# main.net
KiCad netlist of a schematic drawn in EAGLE
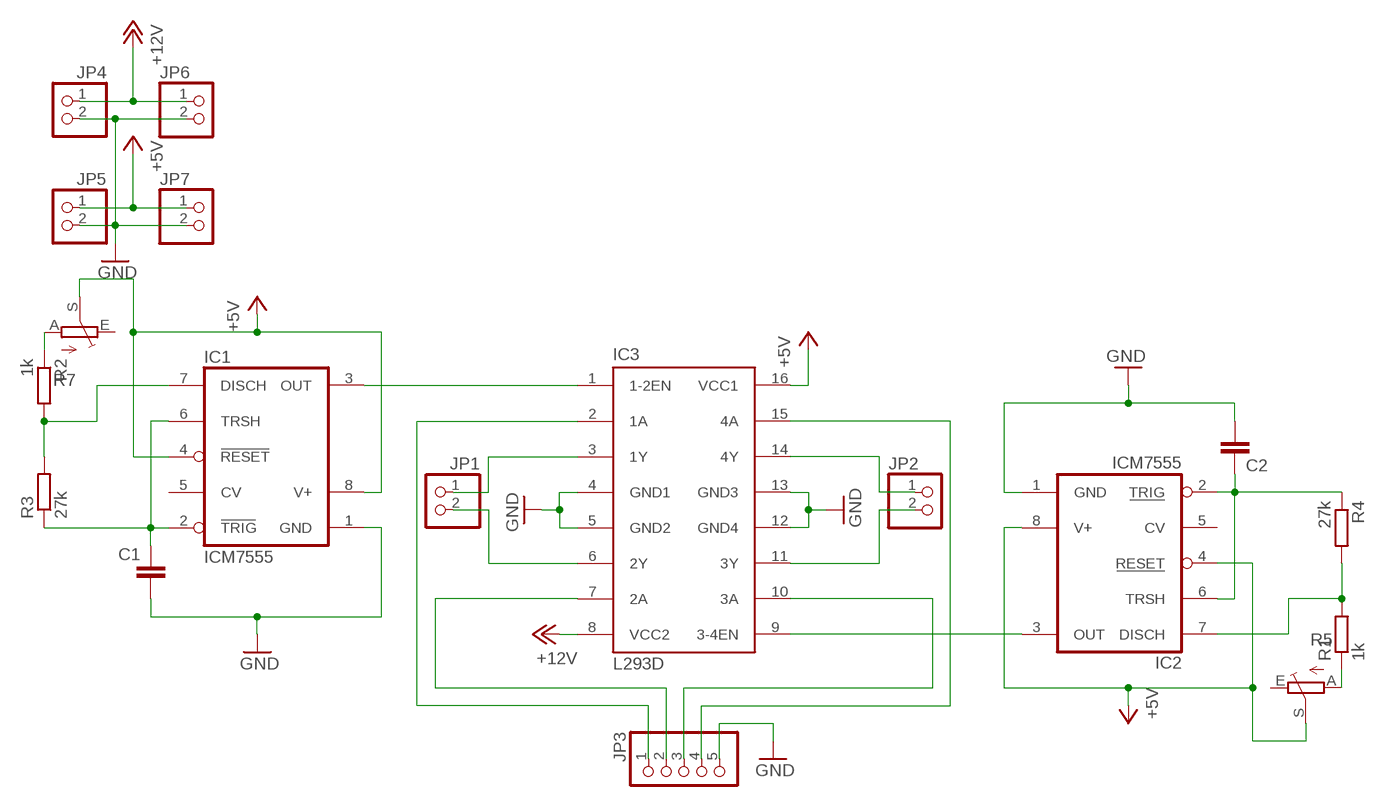
[diagram p0: schematic, sheet 1]

(export (version "E")
  (design (tool "Eeschema 10.0.6"))
  (components
    (comp (ref "C1")
      (value "C-EU025-025X050")
      (footprint "eagle-import:C025-025X050")
      (libsource (lib "eagle-import") (part "C-EU025-025X050"))
    )
    (comp (ref "C2")
      (value "C-EU025-025X050")
      (footprint "eagle-import:C025-025X050")
      (libsource (lib "eagle-import") (part "C-EU025-025X050"))
    )
    (comp (ref "IC1")
      (value "ICM7555")
      (footprint "eagle-import:DIL08")
      (fields (field (name "MF") "MAXIM") (field (name "MPN") "ICM7555IPA+"))
      (libsource (lib "eagle-import") (part "ICM7555"))
    )
    (comp (ref "IC2")
      (value "ICM7555")
      (footprint "eagle-import:DIL08")
      (fields (field (name "MF") "MAXIM") (field (name "MPN") "ICM7555IPA+"))
      (libsource (lib "eagle-import") (part "ICM7555"))
    )
    (comp (ref "IC3")
      (value "L293D")
      (footprint "eagle-import:DIL16")
      (libsource (lib "eagle-import") (part "L293D"))
    )
    (comp (ref "JP1")
      (value "PINHD-1X2")
      (footprint "eagle-import:1X02")
      (libsource (lib "eagle-import") (part "PINHD-1X2"))
    )
    (comp (ref "JP2")
      (value "PINHD-1X2")
      (footprint "eagle-import:1X02")
      (libsource (lib "eagle-import") (part "PINHD-1X2"))
    )
    (comp (ref "JP3")
      (value "PINHD-1X5")
      (footprint "eagle-import:1X05")
      (libsource (lib "eagle-import") (part "PINHD-1X5"))
    )
    (comp (ref "JP4")
      (value "PINHD-1X2")
      (footprint "eagle-import:1X02")
      (libsource (lib "eagle-import") (part "PINHD-1X2"))
    )
    (comp (ref "JP5")
      (value "PINHD-1X2")
      (footprint "eagle-import:1X02")
      (libsource (lib "eagle-import") (part "PINHD-1X2"))
    )
    (comp (ref "JP6")
      (value "PINHD-1X2")
      (footprint "eagle-import:1X02")
      (libsource (lib "eagle-import") (part "PINHD-1X2"))
    )
    (comp (ref "JP7")
      (value "PINHD-1X2")
      (footprint "eagle-import:1X02")
      (libsource (lib "eagle-import") (part "PINHD-1X2"))
    )
    (comp (ref "R1")
      (value "1k")
      (footprint "eagle-import:0204_7")
      (libsource (lib "eagle-import") (part "R-EU_0204/7"))
    )
    (comp (ref "R2")
      (value "1k")
      (footprint "eagle-import:0204_7")
      (libsource (lib "eagle-import") (part "R-EU_0204/7"))
    )
    (comp (ref "R3")
      (value "27k")
      (footprint "eagle-import:0204_7")
      (libsource (lib "eagle-import") (part "R-EU_0204/7"))
    )
    (comp (ref "R4")
      (value "27k")
      (footprint "eagle-import:0204_7")
      (libsource (lib "eagle-import") (part "R-EU_0204/7"))
    )
    (comp (ref "R5")
      (value "TRIM_EU-LI15")
      (footprint "eagle-import:LI15")
      (libsource (lib "eagle-import") (part "TRIM_EU-LI15"))
    )
    (comp (ref "R7")
      (value "TRIM_EU-LI15")
      (footprint "eagle-import:LI15")
      (libsource (lib "eagle-import") (part "TRIM_EU-LI15"))
    )
  )
  (nets
    (net (code "1") (name "+5V") (class "Default")
      (node (ref "IC1") (pin "4") (pinfunction "RESET_4") (pintype "input"))
      (node (ref "IC1") (pin "8") (pinfunction "V+_8") (pintype "power_in"))
      (node (ref "IC2") (pin "4") (pinfunction "RESET_4") (pintype "input"))
      (node (ref "IC2") (pin "8") (pinfunction "V+_8") (pintype "power_in"))
      (node (ref "IC3") (pin "16") (pinfunction "VCC1_16") (pintype "power_in"))
      (node (ref "JP5") (pin "1") (pinfunction "1_1") (pintype "passive"))
      (node (ref "JP7") (pin "1") (pinfunction "1_1") (pintype "passive"))
      (node (ref "R5") (pin "S") (pinfunction "S_S") (pintype "passive"))
      (node (ref "R7") (pin "S") (pinfunction "S_S") (pintype "passive"))
    )
    (net (code "2") (name "+12V") (class "Default")
      (node (ref "IC3") (pin "8") (pinfunction "VCC2_8") (pintype "power_in"))
      (node (ref "JP4") (pin "1") (pinfunction "1_1") (pintype "passive"))
      (node (ref "JP6") (pin "1") (pinfunction "1_1") (pintype "passive"))
    )
    (net (code "3") (name "GND") (class "Default")
      (node (ref "C1") (pin "2") (pinfunction "2_2") (pintype "passive"))
      (node (ref "C2") (pin "2") (pinfunction "2_2") (pintype "passive"))
      (node (ref "IC1") (pin "1") (pinfunction "GND_1") (pintype "power_in"))
      (node (ref "IC2") (pin "1") (pinfunction "GND_1") (pintype "power_in"))
      (node (ref "IC3") (pin "12") (pinfunction "GND4_12") (pintype "power_in"))
      (node (ref "IC3") (pin "13") (pinfunction "GND3_13") (pintype "power_in"))
      (node (ref "IC3") (pin "4") (pinfunction "GND1_4") (pintype "power_in"))
      (node (ref "IC3") (pin "5") (pinfunction "GND2_5") (pintype "power_in"))
      (node (ref "JP3") (pin "5") (pinfunction "5_5") (pintype "passive"))
      (node (ref "JP4") (pin "2") (pinfunction "2_2") (pintype "passive"))
      (node (ref "JP5") (pin "2") (pinfunction "2_2") (pintype "passive"))
      (node (ref "JP6") (pin "2") (pinfunction "2_2") (pintype "passive"))
      (node (ref "JP7") (pin "2") (pinfunction "2_2") (pintype "passive"))
    )
    (net (code "4") (name "Net-(IC1-DISCH)") (class "Default")
      (node (ref "IC1") (pin "7") (pinfunction "DISCH_7") (pintype "input"))
      (node (ref "R2") (pin "2") (pinfunction "2_2") (pintype "passive"))
      (node (ref "R3") (pin "2") (pinfunction "2_2") (pintype "passive"))
    )
    (net (code "5") (name "Net-(IC1-OUT)") (class "Default")
      (node (ref "IC1") (pin "3") (pinfunction "OUT_3") (pintype "output"))
      (node (ref "IC3") (pin "1") (pinfunction "1-2EN_1") (pintype "input"))
    )
    (net (code "6") (name "Net-(IC1-TRIG)") (class "Default")
      (node (ref "C1") (pin "1") (pinfunction "1_1") (pintype "passive"))
      (node (ref "IC1") (pin "2") (pinfunction "TRIG_2") (pintype "bidirectional"))
      (node (ref "IC1") (pin "6") (pinfunction "TRSH_6") (pintype "input"))
      (node (ref "R3") (pin "1") (pinfunction "1_1") (pintype "passive"))
    )
    (net (code "7") (name "Net-(IC2-DISCH)") (class "Default")
      (node (ref "IC2") (pin "7") (pinfunction "DISCH_7") (pintype "input"))
      (node (ref "R1") (pin "2") (pinfunction "2_2") (pintype "passive"))
      (node (ref "R4") (pin "2") (pinfunction "2_2") (pintype "passive"))
    )
    (net (code "8") (name "Net-(IC2-OUT)") (class "Default")
      (node (ref "IC2") (pin "3") (pinfunction "OUT_3") (pintype "output"))
      (node (ref "IC3") (pin "9") (pinfunction "3-4EN_9") (pintype "input"))
    )
    (net (code "9") (name "Net-(IC2-TRIG)") (class "Default")
      (node (ref "C2") (pin "1") (pinfunction "1_1") (pintype "passive"))
      (node (ref "IC2") (pin "2") (pinfunction "TRIG_2") (pintype "bidirectional"))
      (node (ref "IC2") (pin "6") (pinfunction "TRSH_6") (pintype "input"))
      (node (ref "R4") (pin "1") (pinfunction "1_1") (pintype "passive"))
    )
    (net (code "10") (name "Net-(IC3-1A)") (class "Default")
      (node (ref "IC3") (pin "2") (pinfunction "1A_2") (pintype "input"))
      (node (ref "JP3") (pin "1") (pinfunction "1_1") (pintype "passive"))
    )
    (net (code "11") (name "Net-(IC3-1Y)") (class "Default")
      (node (ref "IC3") (pin "3") (pinfunction "1Y_3") (pintype "output"))
      (node (ref "JP1") (pin "1") (pinfunction "1_1") (pintype "passive"))
    )
    (net (code "12") (name "Net-(IC3-2A)") (class "Default")
      (node (ref "IC3") (pin "7") (pinfunction "2A_7") (pintype "input"))
      (node (ref "JP3") (pin "2") (pinfunction "2_2") (pintype "passive"))
    )
    (net (code "13") (name "Net-(IC3-2Y)") (class "Default")
      (node (ref "IC3") (pin "6") (pinfunction "2Y_6") (pintype "output"))
      (node (ref "JP1") (pin "2") (pinfunction "2_2") (pintype "passive"))
    )
    (net (code "14") (name "Net-(IC3-3A)") (class "Default")
      (node (ref "IC3") (pin "10") (pinfunction "3A_10") (pintype "input"))
      (node (ref "JP3") (pin "3") (pinfunction "3_3") (pintype "passive"))
    )
    (net (code "15") (name "Net-(IC3-3Y)") (class "Default")
      (node (ref "IC3") (pin "11") (pinfunction "3Y_11") (pintype "output"))
      (node (ref "JP2") (pin "2") (pinfunction "2_2") (pintype "passive"))
    )
    (net (code "16") (name "Net-(IC3-4A)") (class "Default")
      (node (ref "IC3") (pin "15") (pinfunction "4A_15") (pintype "input"))
      (node (ref "JP3") (pin "4") (pinfunction "4_4") (pintype "passive"))
    )
    (net (code "17") (name "Net-(IC3-4Y)") (class "Default")
      (node (ref "IC3") (pin "14") (pinfunction "4Y_14") (pintype "output"))
      (node (ref "JP2") (pin "1") (pinfunction "1_1") (pintype "passive"))
    )
    (net (code "18") (name "Net-(R1-Pad1)") (class "Default")
      (node (ref "R1") (pin "1") (pinfunction "1_1") (pintype "passive"))
      (node (ref "R5") (pin "A") (pinfunction "A_A") (pintype "passive"))
    )
    (net (code "19") (name "Net-(R2-Pad1)") (class "Default")
      (node (ref "R2") (pin "1") (pinfunction "1_1") (pintype "passive"))
      (node (ref "R7") (pin "A") (pinfunction "A_A") (pintype "passive"))
    )
    (net (code "20") (name "unconnected-(IC1-CV-Pad5)") (class "Default")
      (node (ref "IC1") (pin "5") (pinfunction "CV_5") (pintype "passive"))
    )
    (net (code "21") (name "unconnected-(IC2-CV-Pad5)") (class "Default")
      (node (ref "IC2") (pin "5") (pinfunction "CV_5") (pintype "passive"))
    )
    (net (code "22") (name "unconnected-(R5-PadE)") (class "Default")
      (node (ref "R5") (pin "E") (pinfunction "E_E") (pintype "passive"))
    )
    (net (code "23") (name "unconnected-(R7-PadE)") (class "Default")
      (node (ref "R7") (pin "E") (pinfunction "E_E") (pintype "passive"))
    )
  )
)
